# Input_Connector.net
KiCad netlist of a schematic drawn in Altium Designer
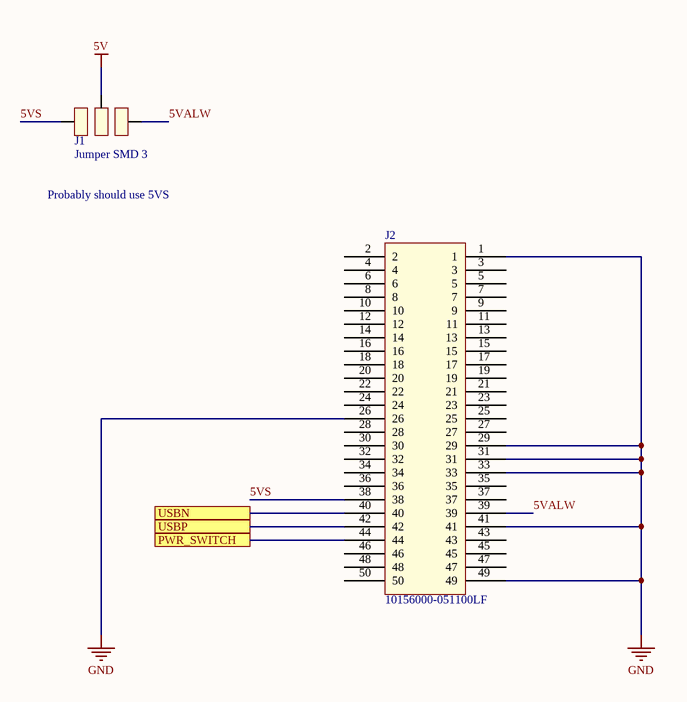
[diagram p0: Input Connector.SchDoc]

(export (version "E")
  (design (tool "Eeschema 10.0.6"))
  (components
    (comp (ref "J1")
      (value "Jumper SMD 3")
      (footprint "Jumper SMD 3")
      (libsource (lib "KBuchka-IntLib") (part "Jumper SMD 3"))
    )
    (comp (ref "J2")
      (value "10156000-051100LF")
      (footprint "10156000-051100LF")
      (libsource (lib "KBuchka-IntLib") (part "10156000-051100LF"))
    )
  )
  (nets
    (net (code "1") (name "/5VALW") (class "Default")
      (node (ref "J1") (pin "1") (pinfunction "1_1") (pintype "passive"))
      (node (ref "J2") (pin "39") (pinfunction "39_39") (pintype "passive"))
    )
    (net (code "2") (name "/5VS") (class "Default")
      (node (ref "J1") (pin "3") (pinfunction "3_3") (pintype "passive"))
      (node (ref "J2") (pin "38") (pinfunction "38_38") (pintype "passive"))
    )
    (net (code "3") (name "/PWR_SWITCH") (class "Default")
      (node (ref "J2") (pin "44") (pinfunction "44_44") (pintype "passive"))
    )
    (net (code "4") (name "/USBN") (class "Default")
      (node (ref "J2") (pin "40") (pinfunction "40_40") (pintype "passive"))
    )
    (net (code "5") (name "/USBP") (class "Default")
      (node (ref "J2") (pin "42") (pinfunction "42_42") (pintype "passive"))
    )
    (net (code "6") (name "5V") (class "Default")
      (node (ref "J1") (pin "2") (pinfunction "2_2") (pintype "passive"))
    )
    (net (code "7") (name "GND") (class "Default")
      (node (ref "J2") (pin "1") (pinfunction "1_1") (pintype "passive"))
      (node (ref "J2") (pin "26") (pinfunction "26_26") (pintype "passive"))
      (node (ref "J2") (pin "29") (pinfunction "29_29") (pintype "passive"))
      (node (ref "J2") (pin "31") (pinfunction "31_31") (pintype "passive"))
      (node (ref "J2") (pin "33") (pinfunction "33_33") (pintype "passive"))
      (node (ref "J2") (pin "41") (pinfunction "41_41") (pintype "passive"))
      (node (ref "J2") (pin "49") (pinfunction "49_49") (pintype "passive"))
    )
    (net (code "8") (name "unconnected-(J2-Pad2)") (class "Default")
      (node (ref "J2") (pin "2") (pinfunction "2_2") (pintype "passive"))
    )
    (net (code "9") (name "unconnected-(J2-Pad3)") (class "Default")
      (node (ref "J2") (pin "3") (pinfunction "3_3") (pintype "passive"))
    )
    (net (code "10") (name "unconnected-(J2-Pad4)") (class "Default")
      (node (ref "J2") (pin "4") (pinfunction "4_4") (pintype "passive"))
    )
    (net (code "11") (name "unconnected-(J2-Pad5)") (class "Default")
      (node (ref "J2") (pin "5") (pinfunction "5_5") (pintype "passive"))
    )
    (net (code "12") (name "unconnected-(J2-Pad6)") (class "Default")
      (node (ref "J2") (pin "6") (pinfunction "6_6") (pintype "passive"))
    )
    (net (code "13") (name "unconnected-(J2-Pad7)") (class "Default")
      (node (ref "J2") (pin "7") (pinfunction "7_7") (pintype "passive"))
    )
    (net (code "14") (name "unconnected-(J2-Pad8)") (class "Default")
      (node (ref "J2") (pin "8") (pinfunction "8_8") (pintype "passive"))
    )
    (net (code "15") (name "unconnected-(J2-Pad9)") (class "Default")
      (node (ref "J2") (pin "9") (pinfunction "9_9") (pintype "passive"))
    )
    (net (code "16") (name "unconnected-(J2-Pad10)") (class "Default")
      (node (ref "J2") (pin "10") (pinfunction "10_10") (pintype "passive"))
    )
    (net (code "17") (name "unconnected-(J2-Pad11)") (class "Default")
      (node (ref "J2") (pin "11") (pinfunction "11_11") (pintype "passive"))
    )
    (net (code "18") (name "unconnected-(J2-Pad12)") (class "Default")
      (node (ref "J2") (pin "12") (pinfunction "12_12") (pintype "passive"))
    )
    (net (code "19") (name "unconnected-(J2-Pad13)") (class "Default")
      (node (ref "J2") (pin "13") (pinfunction "13_13") (pintype "passive"))
    )
    (net (code "20") (name "unconnected-(J2-Pad14)") (class "Default")
      (node (ref "J2") (pin "14") (pinfunction "14_14") (pintype "passive"))
    )
    (net (code "21") (name "unconnected-(J2-Pad15)") (class "Default")
      (node (ref "J2") (pin "15") (pinfunction "15_15") (pintype "passive"))
    )
    (net (code "22") (name "unconnected-(J2-Pad16)") (class "Default")
      (node (ref "J2") (pin "16") (pinfunction "16_16") (pintype "passive"))
    )
    (net (code "23") (name "unconnected-(J2-Pad17)") (class "Default")
      (node (ref "J2") (pin "17") (pinfunction "17_17") (pintype "passive"))
    )
    (net (code "24") (name "unconnected-(J2-Pad18)") (class "Default")
      (node (ref "J2") (pin "18") (pinfunction "18_18") (pintype "passive"))
    )
    (net (code "25") (name "unconnected-(J2-Pad19)") (class "Default")
      (node (ref "J2") (pin "19") (pinfunction "19_19") (pintype "passive"))
    )
    (net (code "26") (name "unconnected-(J2-Pad20)") (class "Default")
      (node (ref "J2") (pin "20") (pinfunction "20_20") (pintype "passive"))
    )
    (net (code "27") (name "unconnected-(J2-Pad21)") (class "Default")
      (node (ref "J2") (pin "21") (pinfunction "21_21") (pintype "passive"))
    )
    (net (code "28") (name "unconnected-(J2-Pad22)") (class "Default")
      (node (ref "J2") (pin "22") (pinfunction "22_22") (pintype "passive"))
    )
    (net (code "29") (name "unconnected-(J2-Pad23)") (class "Default")
      (node (ref "J2") (pin "23") (pinfunction "23_23") (pintype "passive"))
    )
    (net (code "30") (name "unconnected-(J2-Pad24)") (class "Default")
      (node (ref "J2") (pin "24") (pinfunction "24_24") (pintype "passive"))
    )
    (net (code "31") (name "unconnected-(J2-Pad25)") (class "Default")
      (node (ref "J2") (pin "25") (pinfunction "25_25") (pintype "passive"))
    )
    (net (code "32") (name "unconnected-(J2-Pad27)") (class "Default")
      (node (ref "J2") (pin "27") (pinfunction "27_27") (pintype "passive"))
    )
    (net (code "33") (name "unconnected-(J2-Pad28)") (class "Default")
      (node (ref "J2") (pin "28") (pinfunction "28_28") (pintype "passive"))
    )
    (net (code "34") (name "unconnected-(J2-Pad30)") (class "Default")
      (node (ref "J2") (pin "30") (pinfunction "30_30") (pintype "passive"))
    )
    (net (code "35") (name "unconnected-(J2-Pad32)") (class "Default")
      (node (ref "J2") (pin "32") (pinfunction "32_32") (pintype "passive"))
    )
    (net (code "36") (name "unconnected-(J2-Pad34)") (class "Default")
      (node (ref "J2") (pin "34") (pinfunction "34_34") (pintype "passive"))
    )
    (net (code "37") (name "unconnected-(J2-Pad35)") (class "Default")
      (node (ref "J2") (pin "35") (pinfunction "35_35") (pintype "passive"))
    )
    (net (code "38") (name "unconnected-(J2-Pad36)") (class "Default")
      (node (ref "J2") (pin "36") (pinfunction "36_36") (pintype "passive"))
    )
    (net (code "39") (name "unconnected-(J2-Pad37)") (class "Default")
      (node (ref "J2") (pin "37") (pinfunction "37_37") (pintype "passive"))
    )
    (net (code "40") (name "unconnected-(J2-Pad43)") (class "Default")
      (node (ref "J2") (pin "43") (pinfunction "43_43") (pintype "passive"))
    )
    (net (code "41") (name "unconnected-(J2-Pad45)") (class "Default")
      (node (ref "J2") (pin "45") (pinfunction "45_45") (pintype "passive"))
    )
    (net (code "42") (name "unconnected-(J2-Pad46)") (class "Default")
      (node (ref "J2") (pin "46") (pinfunction "46_46") (pintype "passive"))
    )
    (net (code "43") (name "unconnected-(J2-Pad47)") (class "Default")
      (node (ref "J2") (pin "47") (pinfunction "47_47") (pintype "passive"))
    )
    (net (code "44") (name "unconnected-(J2-Pad48)") (class "Default")
      (node (ref "J2") (pin "48") (pinfunction "48_48") (pintype "passive"))
    )
    (net (code "45") (name "unconnected-(J2-Pad50)") (class "Default")
      (node (ref "J2") (pin "50") (pinfunction "50_50") (pintype "passive"))
    )
  )
)
